# MAXII.net
KiCad netlist of a schematic drawn in Altium Designer
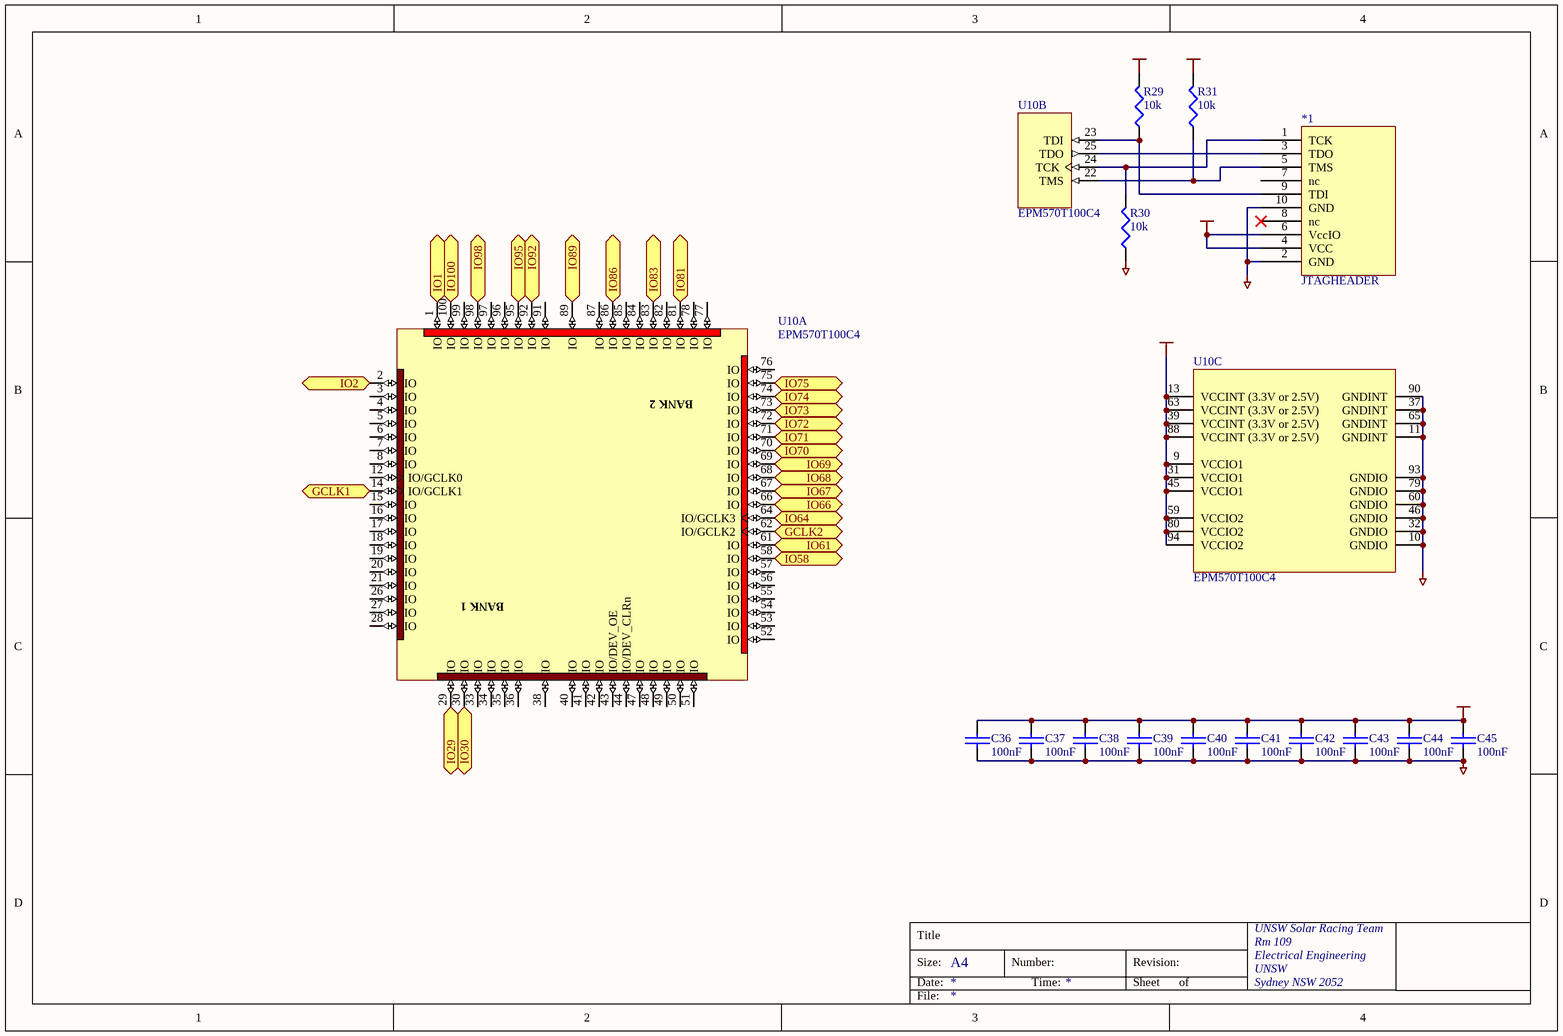
[diagram p0: MAXII.SCHDOC]

(export (version "E")
  (design (tool "Eeschema 10.0.6"))
  (components
    (comp (ref "*1") (value "JTAGHEADER") (footprint "HDR2X5") (libsource (lib "Altera") (part "JTAGHEADER")))
    (comp (ref "C36")
      (value "100nF")
      (footprint "0603")
      (description "Capacitor")
      (libsource (lib "*") (part "CAP"))
    )
    (comp (ref "C37")
      (value "100nF")
      (footprint "0603")
      (description "Capacitor")
      (libsource (lib "*") (part "CAP"))
    )
    (comp (ref "C38")
      (value "100nF")
      (footprint "0603")
      (description "Capacitor")
      (libsource (lib "*") (part "CAP"))
    )
    (comp (ref "C39")
      (value "100nF")
      (footprint "0603")
      (description "Capacitor")
      (libsource (lib "*") (part "CAP"))
    )
    (comp (ref "C40")
      (value "100nF")
      (footprint "0603")
      (description "Capacitor")
      (libsource (lib "*") (part "CAP"))
    )
    (comp (ref "C41")
      (value "100nF")
      (footprint "0603")
      (description "Capacitor")
      (libsource (lib "*") (part "CAP"))
    )
    (comp (ref "C42")
      (value "100nF")
      (footprint "0603")
      (description "Capacitor")
      (libsource (lib "*") (part "CAP"))
    )
    (comp (ref "C43")
      (value "100nF")
      (footprint "0603")
      (description "Capacitor")
      (libsource (lib "*") (part "CAP"))
    )
    (comp (ref "C44")
      (value "100nF")
      (footprint "0603")
      (description "Capacitor")
      (libsource (lib "*") (part "CAP"))
    )
    (comp (ref "C45")
      (value "100nF")
      (footprint "0603")
      (description "Capacitor")
      (libsource (lib "*") (part "CAP"))
    )
    (comp (ref "R29")
      (value "10k")
      (footprint "0603")
      (description "Resistor")
      (libsource (lib "SunswiftLib20030312RR") (part "RES1"))
    )
    (comp (ref "R30")
      (value "10k")
      (footprint "0603")
      (description "Resistor")
      (libsource (lib "SunswiftLib20030312RR") (part "RES1"))
    )
    (comp (ref "R31")
      (value "10k")
      (footprint "0603")
      (description "Resistor")
      (libsource (lib "SunswiftLib20030312RR") (part "RES1"))
    )
    (comp (ref "U10")
      (value "EPM570T100C4")
      (footprint "TQFP100")
      (description "MAX II 2.5/3.3V FPGA, 76 I/Os, 100-Pin Plastic TQFP, Commercial Temperature, Speed Grade 4")
      (fields (field (name "PUBLISHER") "Altium Limited"))
      (libsource (lib "Altera MAX II") (part "EPM570T100C4"))
    )
  )
  (nets
    (net (code "1") (name "/GCLK1") (class "Default")
      (node (ref "U10") (pin "14") (pinfunction "IO/GCLK1_14") (pintype "bidirectional"))
    )
    (net (code "2") (name "/GCLK2") (class "Default")
      (node (ref "U10") (pin "62") (pinfunction "IO/GCLK2_62") (pintype "bidirectional"))
    )
    (net (code "3") (name "/IO1") (class "Default")
      (node (ref "U10") (pin "1") (pinfunction "IO_1") (pintype "bidirectional"))
    )
    (net (code "4") (name "/IO2") (class "Default")
      (node (ref "U10") (pin "2") (pinfunction "IO_2") (pintype "bidirectional"))
    )
    (net (code "5") (name "/IO29") (class "Default")
      (node (ref "U10") (pin "29") (pinfunction "IO_29") (pintype "bidirectional"))
    )
    (net (code "6") (name "/IO30") (class "Default")
      (node (ref "U10") (pin "30") (pinfunction "IO_30") (pintype "bidirectional"))
    )
    (net (code "7") (name "/IO58") (class "Default")
      (node (ref "U10") (pin "58") (pinfunction "IO_58") (pintype "bidirectional"))
    )
    (net (code "8") (name "/IO61") (class "Default")
      (node (ref "U10") (pin "61") (pinfunction "IO_61") (pintype "bidirectional"))
    )
    (net (code "9") (name "/IO64") (class "Default")
      (node (ref "U10") (pin "64") (pinfunction "IO/GCLK3_64") (pintype "bidirectional"))
    )
    (net (code "10") (name "/IO66") (class "Default")
      (node (ref "U10") (pin "66") (pinfunction "IO_66") (pintype "bidirectional"))
    )
    (net (code "11") (name "/IO67") (class "Default")
      (node (ref "U10") (pin "67") (pinfunction "IO_67") (pintype "bidirectional"))
    )
    (net (code "12") (name "/IO68") (class "Default")
      (node (ref "U10") (pin "68") (pinfunction "IO_68") (pintype "bidirectional"))
    )
    (net (code "13") (name "/IO69") (class "Default")
      (node (ref "U10") (pin "69") (pinfunction "IO_69") (pintype "bidirectional"))
    )
    (net (code "14") (name "/IO70") (class "Default")
      (node (ref "U10") (pin "70") (pinfunction "IO_70") (pintype "bidirectional"))
    )
    (net (code "15") (name "/IO71") (class "Default")
      (node (ref "U10") (pin "71") (pinfunction "IO_71") (pintype "bidirectional"))
    )
    (net (code "16") (name "/IO72") (class "Default")
      (node (ref "U10") (pin "72") (pinfunction "IO_72") (pintype "bidirectional"))
    )
    (net (code "17") (name "/IO73") (class "Default")
      (node (ref "U10") (pin "73") (pinfunction "IO_73") (pintype "bidirectional"))
    )
    (net (code "18") (name "/IO74") (class "Default")
      (node (ref "U10") (pin "74") (pinfunction "IO_74") (pintype "bidirectional"))
    )
    (net (code "19") (name "/IO75") (class "Default")
      (node (ref "U10") (pin "75") (pinfunction "IO_75") (pintype "bidirectional"))
    )
    (net (code "20") (name "/IO81") (class "Default")
      (node (ref "U10") (pin "81") (pinfunction "IO_81") (pintype "bidirectional"))
    )
    (net (code "21") (name "/IO83") (class "Default")
      (node (ref "U10") (pin "83") (pinfunction "IO_83") (pintype "bidirectional"))
    )
    (net (code "22") (name "/IO86") (class "Default")
      (node (ref "U10") (pin "86") (pinfunction "IO_86") (pintype "bidirectional"))
    )
    (net (code "23") (name "/IO89") (class "Default")
      (node (ref "U10") (pin "89") (pinfunction "IO_89") (pintype "bidirectional"))
    )
    (net (code "24") (name "/IO92") (class "Default")
      (node (ref "U10") (pin "92") (pinfunction "IO_92") (pintype "bidirectional"))
    )
    (net (code "25") (name "/IO95") (class "Default")
      (node (ref "U10") (pin "95") (pinfunction "IO_95") (pintype "bidirectional"))
    )
    (net (code "26") (name "/IO98") (class "Default")
      (node (ref "U10") (pin "98") (pinfunction "IO_98") (pintype "bidirectional"))
    )
    (net (code "27") (name "/IO100") (class "Default")
      (node (ref "U10") (pin "100") (pinfunction "IO_100") (pintype "bidirectional"))
    )
    (net (code "28") (name "3V3") (class "Default")
      (node (ref "*1") (pin "4") (pinfunction "VCC_4") (pintype "passive"))
      (node (ref "*1") (pin "6") (pinfunction "VccIO_6") (pintype "passive"))
      (node (ref "C36") (pin "1") (pinfunction "1_1") (pintype "passive"))
      (node (ref "C37") (pin "1") (pinfunction "1_1") (pintype "passive"))
      (node (ref "C38") (pin "1") (pinfunction "1_1") (pintype "passive"))
      (node (ref "C39") (pin "1") (pinfunction "1_1") (pintype "passive"))
      (node (ref "C40") (pin "1") (pinfunction "1_1") (pintype "passive"))
      (node (ref "C41") (pin "1") (pinfunction "1_1") (pintype "passive"))
      (node (ref "C42") (pin "1") (pinfunction "1_1") (pintype "passive"))
      (node (ref "C43") (pin "1") (pinfunction "1_1") (pintype "passive"))
      (node (ref "C44") (pin "1") (pinfunction "1_1") (pintype "passive"))
      (node (ref "C45") (pin "1") (pinfunction "1_1") (pintype "passive"))
      (node (ref "R29") (pin "2") (pinfunction "2_2") (pintype "passive"))
      (node (ref "R31") (pin "2") (pinfunction "2_2") (pintype "passive"))
      (node (ref "U10") (pin "13") (pinfunction "VCCINT_(3.3V_or_2.5V)_13") (pintype "power_in"))
      (node (ref "U10") (pin "31") (pinfunction "VCCIO1_31") (pintype "power_in"))
      (node (ref "U10") (pin "39") (pinfunction "VCCINT_(3.3V_or_2.5V)_39") (pintype "power_in"))
      (node (ref "U10") (pin "45") (pinfunction "VCCIO1_45") (pintype "power_in"))
      (node (ref "U10") (pin "59") (pinfunction "VCCIO2_59") (pintype "power_in"))
      (node (ref "U10") (pin "63") (pinfunction "VCCINT_(3.3V_or_2.5V)_63") (pintype "power_in"))
      (node (ref "U10") (pin "80") (pinfunction "VCCIO2_80") (pintype "power_in"))
      (node (ref "U10") (pin "88") (pinfunction "VCCINT_(3.3V_or_2.5V)_88") (pintype "power_in"))
      (node (ref "U10") (pin "9") (pinfunction "VCCIO1_9") (pintype "power_in"))
      (node (ref "U10") (pin "94") (pinfunction "VCCIO2_94") (pintype "power_in"))
    )
    (net (code "29") (name "GND") (class "Default")
      (node (ref "*1") (pin "10") (pinfunction "GND_10") (pintype "passive"))
      (node (ref "*1") (pin "2") (pinfunction "GND_2") (pintype "passive"))
      (node (ref "C36") (pin "2") (pinfunction "2_2") (pintype "passive"))
      (node (ref "C37") (pin "2") (pinfunction "2_2") (pintype "passive"))
      (node (ref "C38") (pin "2") (pinfunction "2_2") (pintype "passive"))
      (node (ref "C39") (pin "2") (pinfunction "2_2") (pintype "passive"))
      (node (ref "C40") (pin "2") (pinfunction "2_2") (pintype "passive"))
      (node (ref "C41") (pin "2") (pinfunction "2_2") (pintype "passive"))
      (node (ref "C42") (pin "2") (pinfunction "2_2") (pintype "passive"))
      (node (ref "C43") (pin "2") (pinfunction "2_2") (pintype "passive"))
      (node (ref "C44") (pin "2") (pinfunction "2_2") (pintype "passive"))
      (node (ref "C45") (pin "2") (pinfunction "2_2") (pintype "passive"))
      (node (ref "R30") (pin "1") (pinfunction "1_1") (pintype "passive"))
      (node (ref "U10") (pin "10") (pinfunction "GNDIO_10") (pintype "power_in"))
      (node (ref "U10") (pin "11") (pinfunction "GNDINT_11") (pintype "power_in"))
      (node (ref "U10") (pin "32") (pinfunction "GNDIO_32") (pintype "power_in"))
      (node (ref "U10") (pin "37") (pinfunction "GNDINT_37") (pintype "power_in"))
      (node (ref "U10") (pin "46") (pinfunction "GNDIO_46") (pintype "power_in"))
      (node (ref "U10") (pin "60") (pinfunction "GNDIO_60") (pintype "power_in"))
      (node (ref "U10") (pin "65") (pinfunction "GNDINT_65") (pintype "power_in"))
      (node (ref "U10") (pin "79") (pinfunction "GNDIO_79") (pintype "power_in"))
      (node (ref "U10") (pin "90") (pinfunction "GNDINT_90") (pintype "power_in"))
      (node (ref "U10") (pin "93") (pinfunction "GNDIO_93") (pintype "power_in"))
    )
    (net (code "30") (name "Net-(*1-TCK)") (class "Default")
      (node (ref "*1") (pin "1") (pinfunction "TCK_1") (pintype "passive"))
      (node (ref "R30") (pin "2") (pinfunction "2_2") (pintype "passive"))
      (node (ref "U10") (pin "24") (pinfunction "TCK_24") (pintype "input"))
    )
    (net (code "31") (name "Net-(*1-TDI)") (class "Default")
      (node (ref "*1") (pin "9") (pinfunction "TDI_9") (pintype "passive"))
      (node (ref "R29") (pin "1") (pinfunction "1_1") (pintype "passive"))
      (node (ref "U10") (pin "23") (pinfunction "TDI_23") (pintype "input"))
    )
    (net (code "32") (name "Net-(*1-TDO)") (class "Default")
      (node (ref "*1") (pin "3") (pinfunction "TDO_3") (pintype "passive"))
      (node (ref "U10") (pin "25") (pinfunction "TDO_25") (pintype "output"))
    )
    (net (code "33") (name "Net-(*1-TMS)") (class "Default")
      (node (ref "*1") (pin "5") (pinfunction "TMS_5") (pintype "passive"))
      (node (ref "R31") (pin "1") (pinfunction "1_1") (pintype "passive"))
      (node (ref "U10") (pin "22") (pinfunction "TMS_22") (pintype "input"))
    )
    (net (code "34") (name "unconnected-(*1-nc-Pad7)") (class "Default")
      (node (ref "*1") (pin "7") (pinfunction "nc_7") (pintype "passive"))
    )
    (net (code "35") (name "unconnected-(*1-nc-Pad8)") (class "Default")
      (node (ref "*1") (pin "8") (pinfunction "nc_8") (pintype "passive+no_connect"))
    )
    (net (code "36") (name "unconnected-(U10A-IO-Pad3)") (class "Default")
      (node (ref "U10") (pin "3") (pinfunction "IO_3") (pintype "bidirectional"))
    )
    (net (code "37") (name "unconnected-(U10A-IO-Pad4)") (class "Default")
      (node (ref "U10") (pin "4") (pinfunction "IO_4") (pintype "bidirectional"))
    )
    (net (code "38") (name "unconnected-(U10A-IO-Pad5)") (class "Default")
      (node (ref "U10") (pin "5") (pinfunction "IO_5") (pintype "bidirectional"))
    )
    (net (code "39") (name "unconnected-(U10A-IO-Pad6)") (class "Default")
      (node (ref "U10") (pin "6") (pinfunction "IO_6") (pintype "bidirectional"))
    )
    (net (code "40") (name "unconnected-(U10A-IO-Pad7)") (class "Default")
      (node (ref "U10") (pin "7") (pinfunction "IO_7") (pintype "bidirectional"))
    )
    (net (code "41") (name "unconnected-(U10A-IO-Pad8)") (class "Default")
      (node (ref "U10") (pin "8") (pinfunction "IO_8") (pintype "bidirectional"))
    )
    (net (code "42") (name "unconnected-(U10A-IO-Pad15)") (class "Default")
      (node (ref "U10") (pin "15") (pinfunction "IO_15") (pintype "bidirectional"))
    )
    (net (code "43") (name "unconnected-(U10A-IO-Pad16)") (class "Default")
      (node (ref "U10") (pin "16") (pinfunction "IO_16") (pintype "bidirectional"))
    )
    (net (code "44") (name "unconnected-(U10A-IO-Pad17)") (class "Default")
      (node (ref "U10") (pin "17") (pinfunction "IO_17") (pintype "bidirectional"))
    )
    (net (code "45") (name "unconnected-(U10A-IO-Pad18)") (class "Default")
      (node (ref "U10") (pin "18") (pinfunction "IO_18") (pintype "bidirectional"))
    )
    (net (code "46") (name "unconnected-(U10A-IO-Pad19)") (class "Default")
      (node (ref "U10") (pin "19") (pinfunction "IO_19") (pintype "bidirectional"))
    )
    (net (code "47") (name "unconnected-(U10A-IO-Pad20)") (class "Default")
      (node (ref "U10") (pin "20") (pinfunction "IO_20") (pintype "bidirectional"))
    )
    (net (code "48") (name "unconnected-(U10A-IO-Pad21)") (class "Default")
      (node (ref "U10") (pin "21") (pinfunction "IO_21") (pintype "bidirectional"))
    )
    (net (code "49") (name "unconnected-(U10A-IO-Pad26)") (class "Default")
      (node (ref "U10") (pin "26") (pinfunction "IO_26") (pintype "bidirectional"))
    )
    (net (code "50") (name "unconnected-(U10A-IO-Pad27)") (class "Default")
      (node (ref "U10") (pin "27") (pinfunction "IO_27") (pintype "bidirectional"))
    )
    (net (code "51") (name "unconnected-(U10A-IO-Pad28)") (class "Default")
      (node (ref "U10") (pin "28") (pinfunction "IO_28") (pintype "bidirectional"))
    )
    (net (code "52") (name "unconnected-(U10A-IO-Pad33)") (class "Default")
      (node (ref "U10") (pin "33") (pinfunction "IO_33") (pintype "bidirectional"))
    )
    (net (code "53") (name "unconnected-(U10A-IO-Pad34)") (class "Default")
      (node (ref "U10") (pin "34") (pinfunction "IO_34") (pintype "bidirectional"))
    )
    (net (code "54") (name "unconnected-(U10A-IO-Pad35)") (class "Default")
      (node (ref "U10") (pin "35") (pinfunction "IO_35") (pintype "bidirectional"))
    )
    (net (code "55") (name "unconnected-(U10A-IO-Pad36)") (class "Default")
      (node (ref "U10") (pin "36") (pinfunction "IO_36") (pintype "bidirectional"))
    )
    (net (code "56") (name "unconnected-(U10A-IO-Pad38)") (class "Default")
      (node (ref "U10") (pin "38") (pinfunction "IO_38") (pintype "bidirectional"))
    )
    (net (code "57") (name "unconnected-(U10A-IO-Pad40)") (class "Default")
      (node (ref "U10") (pin "40") (pinfunction "IO_40") (pintype "bidirectional"))
    )
    (net (code "58") (name "unconnected-(U10A-IO-Pad41)") (class "Default")
      (node (ref "U10") (pin "41") (pinfunction "IO_41") (pintype "bidirectional"))
    )
    (net (code "59") (name "unconnected-(U10A-IO-Pad42)") (class "Default")
      (node (ref "U10") (pin "42") (pinfunction "IO_42") (pintype "bidirectional"))
    )
    (net (code "60") (name "unconnected-(U10A-IO-Pad47)") (class "Default")
      (node (ref "U10") (pin "47") (pinfunction "IO_47") (pintype "bidirectional"))
    )
    (net (code "61") (name "unconnected-(U10A-IO-Pad48)") (class "Default")
      (node (ref "U10") (pin "48") (pinfunction "IO_48") (pintype "bidirectional"))
    )
    (net (code "62") (name "unconnected-(U10A-IO-Pad49)") (class "Default")
      (node (ref "U10") (pin "49") (pinfunction "IO_49") (pintype "bidirectional"))
    )
    (net (code "63") (name "unconnected-(U10A-IO-Pad50)") (class "Default")
      (node (ref "U10") (pin "50") (pinfunction "IO_50") (pintype "bidirectional"))
    )
    (net (code "64") (name "unconnected-(U10A-IO-Pad51)") (class "Default")
      (node (ref "U10") (pin "51") (pinfunction "IO_51") (pintype "bidirectional"))
    )
    (net (code "65") (name "unconnected-(U10A-IO-Pad52)") (class "Default")
      (node (ref "U10") (pin "52") (pinfunction "IO_52") (pintype "bidirectional"))
    )
    (net (code "66") (name "unconnected-(U10A-IO-Pad53)") (class "Default")
      (node (ref "U10") (pin "53") (pinfunction "IO_53") (pintype "bidirectional"))
    )
    (net (code "67") (name "unconnected-(U10A-IO-Pad54)") (class "Default")
      (node (ref "U10") (pin "54") (pinfunction "IO_54") (pintype "bidirectional"))
    )
    (net (code "68") (name "unconnected-(U10A-IO-Pad55)") (class "Default")
      (node (ref "U10") (pin "55") (pinfunction "IO_55") (pintype "bidirectional"))
    )
    (net (code "69") (name "unconnected-(U10A-IO-Pad56)") (class "Default")
      (node (ref "U10") (pin "56") (pinfunction "IO_56") (pintype "bidirectional"))
    )
    (net (code "70") (name "unconnected-(U10A-IO-Pad57)") (class "Default")
      (node (ref "U10") (pin "57") (pinfunction "IO_57") (pintype "bidirectional"))
    )
    (net (code "71") (name "unconnected-(U10A-IO-Pad76)") (class "Default")
      (node (ref "U10") (pin "76") (pinfunction "IO_76") (pintype "bidirectional"))
    )
    (net (code "72") (name "unconnected-(U10A-IO-Pad77)") (class "Default")
      (node (ref "U10") (pin "77") (pinfunction "IO_77") (pintype "bidirectional"))
    )
    (net (code "73") (name "unconnected-(U10A-IO-Pad78)") (class "Default")
      (node (ref "U10") (pin "78") (pinfunction "IO_78") (pintype "bidirectional"))
    )
    (net (code "74") (name "unconnected-(U10A-IO-Pad82)") (class "Default")
      (node (ref "U10") (pin "82") (pinfunction "IO_82") (pintype "bidirectional"))
    )
    (net (code "75") (name "unconnected-(U10A-IO-Pad84)") (class "Default")
      (node (ref "U10") (pin "84") (pinfunction "IO_84") (pintype "bidirectional"))
    )
    (net (code "76") (name "unconnected-(U10A-IO-Pad85)") (class "Default")
      (node (ref "U10") (pin "85") (pinfunction "IO_85") (pintype "bidirectional"))
    )
    (net (code "77") (name "unconnected-(U10A-IO-Pad87)") (class "Default")
      (node (ref "U10") (pin "87") (pinfunction "IO_87") (pintype "bidirectional"))
    )
    (net (code "78") (name "unconnected-(U10A-IO-Pad91)") (class "Default")
      (node (ref "U10") (pin "91") (pinfunction "IO_91") (pintype "bidirectional"))
    )
    (net (code "79") (name "unconnected-(U10A-IO-Pad96)") (class "Default")
      (node (ref "U10") (pin "96") (pinfunction "IO_96") (pintype "bidirectional"))
    )
    (net (code "80") (name "unconnected-(U10A-IO-Pad97)") (class "Default")
      (node (ref "U10") (pin "97") (pinfunction "IO_97") (pintype "bidirectional"))
    )
    (net (code "81") (name "unconnected-(U10A-IO-Pad99)") (class "Default")
      (node (ref "U10") (pin "99") (pinfunction "IO_99") (pintype "bidirectional"))
    )
    (net (code "82") (name "unconnected-(U10A-IO{slash}DEV_CLRn-Pad44)") (class "Default")
      (node (ref "U10") (pin "44") (pinfunction "IO/DEV_CLRn_44") (pintype "bidirectional"))
    )
    (net (code "83") (name "unconnected-(U10A-IO{slash}DEV_OE-Pad43)") (class "Default")
      (node (ref "U10") (pin "43") (pinfunction "IO/DEV_OE_43") (pintype "bidirectional"))
    )
    (net (code "84") (name "unconnected-(U10A-IO{slash}GCLK0-Pad12)") (class "Default")
      (node (ref "U10") (pin "12") (pinfunction "IO/GCLK0_12") (pintype "bidirectional"))
    )
  )
)
